# thundermaus.net
KiCad netlist of a schematic drawn in EAGLE
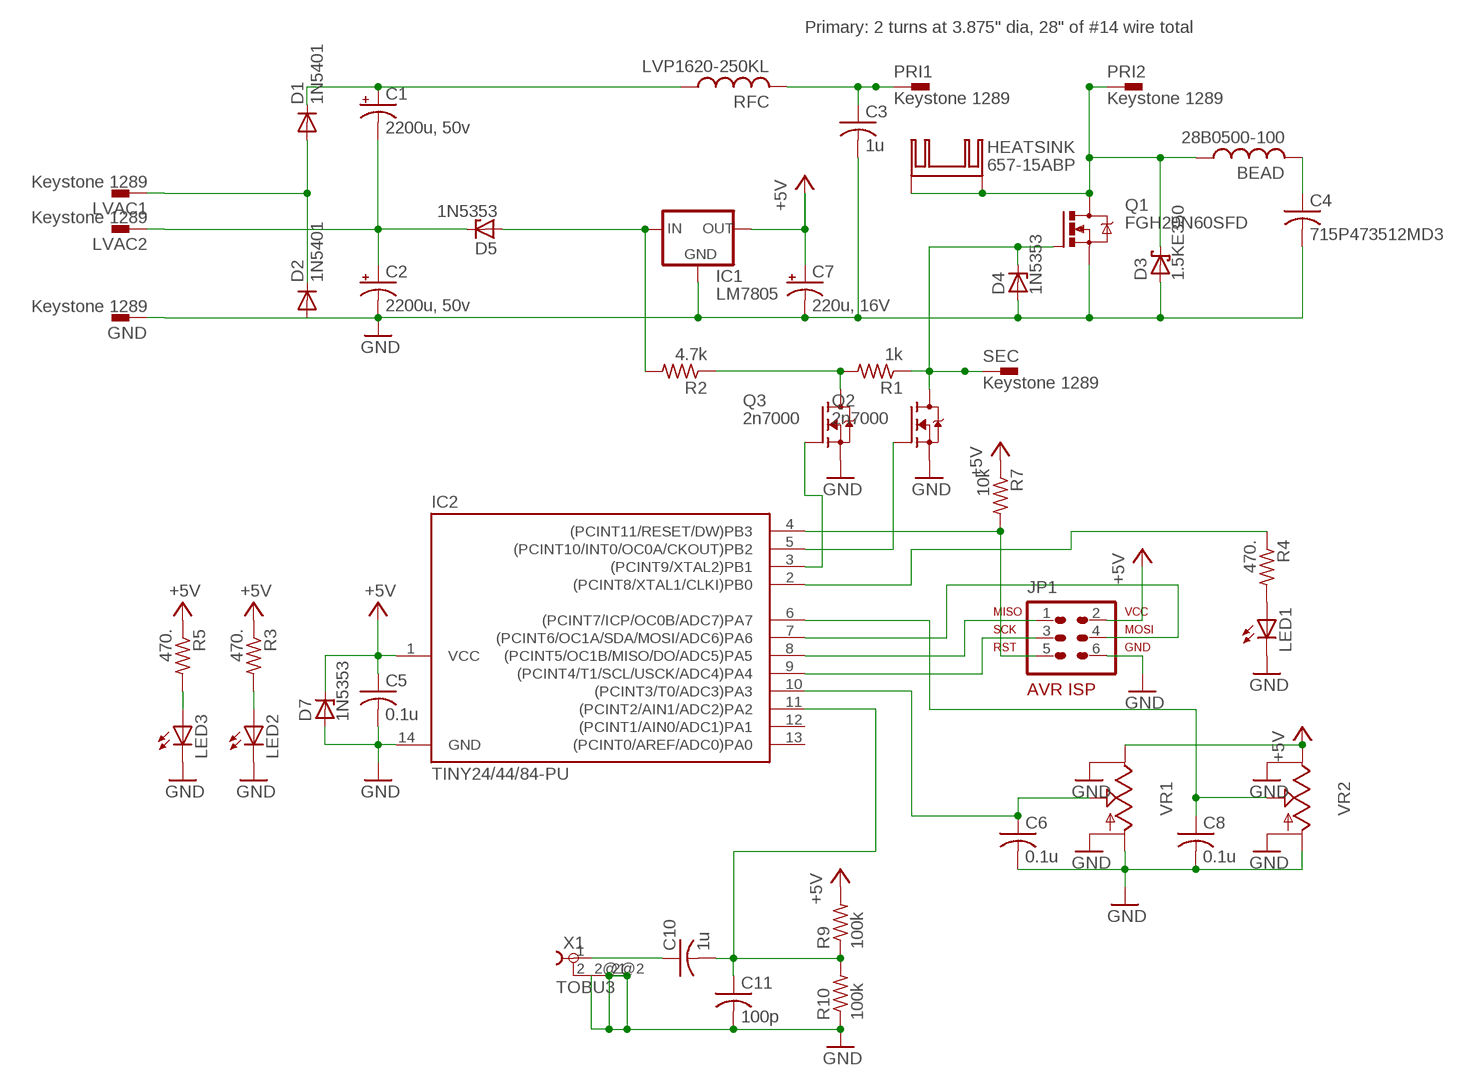
[diagram p0: schematic, sheet 1]

(export (version "E")
  (design (tool "Eeschema 10.0.6"))
  (components
    (comp (ref "BEAD")
      (value "28B0500-100")
      (footprint "eagle-import:0207_10")
      (libsource (lib "eagle-import") (part "L-US0207/10"))
    )
    (comp (ref "C1")
      (value "2200u, 50v")
      (footprint "eagle-import:E7,5-16")
      (libsource (lib "eagle-import") (part "CPOL-USE7.5-16"))
    )
    (comp (ref "C2")
      (value "2200u, 50v")
      (footprint "eagle-import:E7,5-16")
      (libsource (lib "eagle-import") (part "CPOL-USE7.5-16"))
    )
    (comp (ref "C3")
      (value "1u")
      (footprint "eagle-import:C225-062X268")
      (libsource (lib "eagle-import") (part "C-US225-062X268"))
    )
    (comp (ref "C4")
      (value "715P473512MD3")
      (footprint "eagle-import:C325-182X374")
      (libsource (lib "eagle-import") (part "C-US325-182X374"))
    )
    (comp (ref "C5")
      (value "0.1u")
      (footprint "eagle-import:C025-025X050")
      (libsource (lib "eagle-import") (part "C-US025-025X050"))
    )
    (comp (ref "C6")
      (value "0.1u")
      (footprint "eagle-import:C025-025X050")
      (libsource (lib "eagle-import") (part "C-US025-025X050"))
    )
    (comp (ref "C7")
      (value "220u, 16V")
      (footprint "eagle-import:E2,5-7")
      (libsource (lib "eagle-import") (part "CPOL-USE2.5-7"))
    )
    (comp (ref "C8")
      (value "0.1u")
      (footprint "eagle-import:C025-025X050")
      (libsource (lib "eagle-import") (part "C-US025-025X050"))
    )
    (comp (ref "C10")
      (value "1u")
      (footprint "eagle-import:C025-025X050")
      (libsource (lib "eagle-import") (part "C-US025-025X050"))
    )
    (comp (ref "C11")
      (value "100p")
      (footprint "eagle-import:C025-025X050")
      (libsource (lib "eagle-import") (part "C-US025-025X050"))
    )
    (comp (ref "D1")
      (value "1N5401")
      (footprint "eagle-import:DO201-15")
      (libsource (lib "eagle-import") (part "1N5400"))
    )
    (comp (ref "D2")
      (value "1N5401")
      (footprint "eagle-import:DO201-15")
      (libsource (lib "eagle-import") (part "1N5400"))
    )
    (comp (ref "D3")
      (value "1.5KE350")
      (footprint "eagle-import:DO201T15")
      (libsource (lib "eagle-import") (part "15KEXXD"))
    )
    (comp (ref "D4")
      (value "1N5353")
      (footprint "eagle-import:C1702-15")
      (libsource (lib "eagle-import") (part "1N5333"))
    )
    (comp (ref "D5")
      (value "1N5353")
      (footprint "eagle-import:C1702-15")
      (libsource (lib "eagle-import") (part "1N5333"))
    )
    (comp (ref "D7")
      (value "1N5353")
      (footprint "eagle-import:C1702-15")
      (libsource (lib "eagle-import") (part "1N5333"))
    )
    (comp (ref "GND")
      (value "Keystone 1289")
      (footprint "eagle-import:F061.060")
      (libsource (lib "eagle-import") (part "PIN2F061.060"))
    )
    (comp (ref "HEATSINK")
      (value "657-15ABP")
      (footprint "eagle-import:SK129")
      (libsource (lib "eagle-import") (part "SK129-PAD"))
    )
    (comp (ref "IC1")
      (value "LM7805")
      (footprint "eagle-import:78XXS")
      (libsource (lib "eagle-import") (part "78XXS"))
    )
    (comp (ref "IC2")
      (value "TINY24/44/84-PU")
      (footprint "eagle-import:DIL14")
      (libsource (lib "eagle-import") (part "TINY24/44/84-PU"))
    )
    (comp (ref "JP1")
      (value "AVR-ISP-6VERT")
      (footprint "eagle-import:AVR-ISP-6")
      (libsource (lib "eagle-import") (part "AVR-ISP-6VERT"))
    )
    (comp (ref "LED1")
      (value "LED5MM")
      (footprint "eagle-import:LED5MM")
      (libsource (lib "eagle-import") (part "LED5MM"))
    )
    (comp (ref "LED2")
      (value "LED5MM")
      (footprint "eagle-import:LED5MM")
      (libsource (lib "eagle-import") (part "LED5MM"))
    )
    (comp (ref "LED3")
      (value "LED5MM")
      (footprint "eagle-import:LED5MM")
      (libsource (lib "eagle-import") (part "LED5MM"))
    )
    (comp (ref "LVAC1")
      (value "Keystone 1289")
      (footprint "eagle-import:F061.060")
      (libsource (lib "eagle-import") (part "PIN2F061.060"))
    )
    (comp (ref "LVAC2")
      (value "Keystone 1289")
      (footprint "eagle-import:F061.060")
      (libsource (lib "eagle-import") (part "PIN2F061.060"))
    )
    (comp (ref "PRI1")
      (value "Keystone 1289")
      (footprint "eagle-import:F061.060")
      (libsource (lib "eagle-import") (part "PIN2F061.060"))
    )
    (comp (ref "PRI2")
      (value "Keystone 1289")
      (footprint "eagle-import:F061.060")
      (libsource (lib "eagle-import") (part "PIN2F061.060"))
    )
    (comp (ref "Q1")
      (value "FGH20N60SFD")
      (footprint "eagle-import:TO247BV")
      (libsource (lib "eagle-import") (part "IRFPC40"))
    )
    (comp (ref "Q2")
      (value "2n7000")
      (footprint "eagle-import:TO237-SW")
      (libsource (lib "eagle-import") (part "2N7000"))
    )
    (comp (ref "Q3")
      (value "2n7000")
      (footprint "eagle-import:TO237-SW")
      (libsource (lib "eagle-import") (part "2N7000"))
    )
    (comp (ref "R1")
      (value "1k")
      (footprint "eagle-import:0207_10")
      (libsource (lib "eagle-import") (part "R-US_0207/10"))
    )
    (comp (ref "R2")
      (value "4.7k")
      (footprint "eagle-import:0207_10")
      (libsource (lib "eagle-import") (part "R-US_0207/10"))
    )
    (comp (ref "R3")
      (value "470.")
      (footprint "eagle-import:0207_10")
      (libsource (lib "eagle-import") (part "R-US_0207/10"))
    )
    (comp (ref "R4")
      (value "470.")
      (footprint "eagle-import:0207_10")
      (libsource (lib "eagle-import") (part "R-US_0207/10"))
    )
    (comp (ref "R5")
      (value "470.")
      (footprint "eagle-import:0207_10")
      (libsource (lib "eagle-import") (part "R-US_0207/10"))
    )
    (comp (ref "R7")
      (value "10k")
      (footprint "eagle-import:0207_10")
      (libsource (lib "eagle-import") (part "R-US_0207/10"))
    )
    (comp (ref "R9")
      (value "100k")
      (footprint "eagle-import:0207_10")
      (libsource (lib "eagle-import") (part "R-US_0207/10"))
    )
    (comp (ref "R10")
      (value "100k")
      (footprint "eagle-import:0207_10")
      (libsource (lib "eagle-import") (part "R-US_0207/10"))
    )
    (comp (ref "RFC")
      (value "LVP1620-250KL")
      (footprint "eagle-import:TJ4-U1")
      (libsource (lib "eagle-import") (part "L-USTJ4-U1"))
    )
    (comp (ref "SEC")
      (value "Keystone 1289")
      (footprint "eagle-import:F061.060")
      (libsource (lib "eagle-import") (part "PIN2F061.060"))
    )
    (comp (ref "VR1")
      (value "PTV09")
      (footprint "eagle-import:PTV09")
      (libsource (lib "eagle-import") (part "PTV09"))
    )
    (comp (ref "VR2")
      (value "PTV09")
      (footprint "eagle-import:PTV09")
      (libsource (lib "eagle-import") (part "PTV09"))
    )
    (comp (ref "X1")
      (value "TOBU3")
      (footprint "eagle-import:TOBU3")
      (libsource (lib "eagle-import") (part "TOBU3"))
    )
  )
  (nets
    (net (code "1") (name "+5V") (class "Default")
      (node (ref "C5") (pin "1") (pinfunction "1_1") (pintype "passive"))
      (node (ref "C7") (pin "+") (pinfunction "+_+") (pintype "passive"))
      (node (ref "D7") (pin "C") (pinfunction "C_C") (pintype "passive"))
      (node (ref "IC1") (pin "OUT") (pinfunction "OUT_OUT") (pintype "passive"))
      (node (ref "IC2") (pin "1") (pinfunction "VCC_1") (pintype "power_in"))
      (node (ref "JP1") (pin "2") (pinfunction "2_2") (pintype "passive"))
      (node (ref "R3") (pin "1") (pinfunction "1_1") (pintype "passive"))
      (node (ref "R5") (pin "1") (pinfunction "1_1") (pintype "passive"))
      (node (ref "R7") (pin "1") (pinfunction "1_1") (pintype "passive"))
      (node (ref "R9") (pin "2") (pinfunction "2_2") (pintype "passive"))
      (node (ref "VR1") (pin "P1") (pinfunction "E_P1") (pintype "passive"))
      (node (ref "VR2") (pin "P1") (pinfunction "E_P1") (pintype "passive"))
    )
    (net (code "2") (name "GND") (class "Default")
      (node (ref "C11") (pin "2") (pinfunction "2_2") (pintype "passive"))
      (node (ref "C2") (pin "-") (pinfunction "-_-") (pintype "passive"))
      (node (ref "C3") (pin "2") (pinfunction "2_2") (pintype "passive"))
      (node (ref "C4") (pin "2") (pinfunction "2_2") (pintype "passive"))
      (node (ref "C5") (pin "2") (pinfunction "2_2") (pintype "passive"))
      (node (ref "C6") (pin "2") (pinfunction "2_2") (pintype "passive"))
      (node (ref "C7") (pin "-") (pinfunction "-_-") (pintype "passive"))
      (node (ref "C8") (pin "2") (pinfunction "2_2") (pintype "passive"))
      (node (ref "D2") (pin "A") (pinfunction "A_A") (pintype "passive"))
      (node (ref "D3") (pin "A") (pinfunction "A_A") (pintype "passive"))
      (node (ref "D4") (pin "A") (pinfunction "A_A") (pintype "passive"))
      (node (ref "D7") (pin "A") (pinfunction "A_A") (pintype "passive"))
      (node (ref "GND") (pin "A1") (pinfunction "1_A1") (pintype "passive"))
      (node (ref "GND") (pin "A2") (pinfunction "1.1_A2") (pintype "passive"))
      (node (ref "IC1") (pin "GND") (pinfunction "GND_GND") (pintype "input"))
      (node (ref "IC2") (pin "14") (pinfunction "GND_14") (pintype "power_in"))
      (node (ref "JP1") (pin "6") (pinfunction "6_6") (pintype "passive"))
      (node (ref "LED1") (pin "K") (pinfunction "C_K") (pintype "passive"))
      (node (ref "LED2") (pin "K") (pinfunction "C_K") (pintype "passive"))
      (node (ref "LED3") (pin "K") (pinfunction "C_K") (pintype "passive"))
      (node (ref "Q1") (pin "S") (pinfunction "S_S") (pintype "passive"))
      (node (ref "Q2") (pin "3") (pinfunction "S_3") (pintype "passive"))
      (node (ref "Q3") (pin "3") (pinfunction "S_3") (pintype "passive"))
      (node (ref "R10") (pin "1") (pinfunction "1_1") (pintype "passive"))
      (node (ref "VR1") (pin "P$4") (pinfunction "P$2_P$4") (pintype "passive"))
      (node (ref "VR1") (pin "P$5") (pinfunction "P$1_P$5") (pintype "passive"))
      (node (ref "VR1") (pin "P3") (pinfunction "A_P3") (pintype "passive"))
      (node (ref "VR2") (pin "P$4") (pinfunction "P$2_P$4") (pintype "passive"))
      (node (ref "VR2") (pin "P$5") (pinfunction "P$1_P$5") (pintype "passive"))
      (node (ref "VR2") (pin "P3") (pinfunction "A_P3") (pintype "passive"))
      (node (ref "X1") (pin "2") (pinfunction "2_2") (pintype "passive"))
      (node (ref "X1") (pin "2@1") (pinfunction "3_2@1") (pintype "passive"))
      (node (ref "X1") (pin "2@2") (pinfunction "4_2@2") (pintype "passive"))
    )
    (net (code "3") (name "Net-(BEAD-Pad2)") (class "Default")
      (node (ref "BEAD") (pin "2") (pinfunction "2_2") (pintype "passive"))
      (node (ref "C4") (pin "1") (pinfunction "1_1") (pintype "passive"))
    )
    (net (code "4") (name "Net-(C1-Pad+)") (class "Default")
      (node (ref "C1") (pin "+") (pinfunction "+_+") (pintype "passive"))
      (node (ref "D1") (pin "C") (pinfunction "C_C") (pintype "passive"))
      (node (ref "RFC") (pin "1") (pinfunction "1_1") (pintype "passive"))
    )
    (net (code "5") (name "Net-(C10-Pad1)") (class "Default")
      (node (ref "C10") (pin "1") (pinfunction "1_1") (pintype "passive"))
      (node (ref "X1") (pin "1") (pinfunction "1_1") (pintype "passive"))
    )
    (net (code "6") (name "Net-(D5-PadA)") (class "Default")
      (node (ref "D5") (pin "A") (pinfunction "A_A") (pintype "passive"))
      (node (ref "IC1") (pin "IN") (pinfunction "IN_IN") (pintype "input"))
      (node (ref "R2") (pin "2") (pinfunction "2_2") (pintype "passive"))
    )
    (net (code "7") (name "Net-(IC2-(PCINT2{slash}AIN1{slash}ADC2)PA2)") (class "Default")
      (node (ref "C10") (pin "2") (pinfunction "2_2") (pintype "passive"))
      (node (ref "C11") (pin "1") (pinfunction "1_1") (pintype "passive"))
      (node (ref "IC2") (pin "11") (pinfunction "(PCINT2/AIN1/ADC2)PA2_11") (pintype "bidirectional"))
      (node (ref "R10") (pin "2") (pinfunction "2_2") (pintype "passive"))
      (node (ref "R9") (pin "1") (pinfunction "1_1") (pintype "passive"))
    )
    (net (code "8") (name "Net-(IC2-(PCINT3{slash}T0{slash}ADC3)PA3)") (class "Default")
      (node (ref "C6") (pin "1") (pinfunction "1_1") (pintype "passive"))
      (node (ref "IC2") (pin "10") (pinfunction "(PCINT3/T0/ADC3)PA3_10") (pintype "bidirectional"))
      (node (ref "VR1") (pin "P2") (pinfunction "S_P2") (pintype "passive"))
    )
    (net (code "9") (name "Net-(IC2-(PCINT4{slash}T1{slash}SCL{slash}USCK{slash}ADC4)PA4)") (class "Default")
      (node (ref "IC2") (pin "9") (pinfunction "(PCINT4/T1/SCL/USCK/ADC4)PA4_9") (pintype "bidirectional"))
      (node (ref "JP1") (pin "3") (pinfunction "3_3") (pintype "passive"))
    )
    (net (code "10") (name "Net-(IC2-(PCINT5{slash}OC1B{slash}MISO{slash}DO{slash}ADC5)PA5)") (class "Default")
      (node (ref "IC2") (pin "8") (pinfunction "(PCINT5/OC1B/MISO/DO/ADC5)PA5_8") (pintype "bidirectional"))
      (node (ref "JP1") (pin "1") (pinfunction "1_1") (pintype "passive"))
    )
    (net (code "11") (name "Net-(IC2-(PCINT6{slash}OC1A{slash}SDA{slash}MOSI{slash}ADC6)PA6)") (class "Default")
      (node (ref "IC2") (pin "7") (pinfunction "(PCINT6/OC1A/SDA/MOSI/ADC6)PA6_7") (pintype "bidirectional"))
      (node (ref "JP1") (pin "4") (pinfunction "4_4") (pintype "passive"))
    )
    (net (code "12") (name "Net-(IC2-(PCINT7{slash}ICP{slash}OC0B{slash}ADC7)PA7)") (class "Default")
      (node (ref "C8") (pin "1") (pinfunction "1_1") (pintype "passive"))
      (node (ref "IC2") (pin "6") (pinfunction "(PCINT7/ICP/OC0B/ADC7)PA7_6") (pintype "bidirectional"))
      (node (ref "VR2") (pin "P2") (pinfunction "S_P2") (pintype "passive"))
    )
    (net (code "13") (name "Net-(IC2-(PCINT8{slash}XTAL1{slash}CLKI)PB0)") (class "Default")
      (node (ref "IC2") (pin "2") (pinfunction "(PCINT8/XTAL1/CLKI)PB0_2") (pintype "bidirectional"))
      (node (ref "R4") (pin "1") (pinfunction "1_1") (pintype "passive"))
    )
    (net (code "14") (name "Net-(IC2-(PCINT9{slash}XTAL2)PB1)") (class "Default")
      (node (ref "IC2") (pin "3") (pinfunction "(PCINT9/XTAL2)PB1_3") (pintype "bidirectional"))
      (node (ref "Q3") (pin "2") (pinfunction "G_2") (pintype "passive"))
    )
    (net (code "15") (name "Net-(IC2-(PCINT10{slash}INT0{slash}OC0A{slash}CKOUT)PB2)") (class "Default")
      (node (ref "IC2") (pin "5") (pinfunction "(PCINT10/INT0/OC0A/CKOUT)PB2_5") (pintype "bidirectional"))
      (node (ref "Q2") (pin "2") (pinfunction "G_2") (pintype "passive"))
    )
    (net (code "16") (name "Net-(IC2-(PCINT11{slash}RESET{slash}DW)PB3)") (class "Default")
      (node (ref "IC2") (pin "4") (pinfunction "(PCINT11/RESET/DW)PB3_4") (pintype "bidirectional"))
      (node (ref "JP1") (pin "5") (pinfunction "5_5") (pintype "passive"))
      (node (ref "R7") (pin "2") (pinfunction "2_2") (pintype "passive"))
    )
    (net (code "17") (name "Net-(LED1-PadA)") (class "Default")
      (node (ref "LED1") (pin "A") (pinfunction "A_A") (pintype "passive"))
      (node (ref "R4") (pin "2") (pinfunction "2_2") (pintype "passive"))
    )
    (net (code "18") (name "Net-(LED2-PadA)") (class "Default")
      (node (ref "LED2") (pin "A") (pinfunction "A_A") (pintype "passive"))
      (node (ref "R3") (pin "2") (pinfunction "2_2") (pintype "passive"))
    )
    (net (code "19") (name "Net-(LED3-PadA)") (class "Default")
      (node (ref "LED3") (pin "A") (pinfunction "A_A") (pintype "passive"))
      (node (ref "R5") (pin "2") (pinfunction "2_2") (pintype "passive"))
    )
    (net (code "20") (name "Net-(LVAC1-1)") (class "Default")
      (node (ref "D1") (pin "A") (pinfunction "A_A") (pintype "passive"))
      (node (ref "D2") (pin "C") (pinfunction "C_C") (pintype "passive"))
      (node (ref "LVAC1") (pin "A1") (pinfunction "1_A1") (pintype "passive"))
      (node (ref "LVAC1") (pin "A2") (pinfunction "1.1_A2") (pintype "passive"))
    )
    (net (code "21") (name "Net-(LVAC2-1)") (class "Default")
      (node (ref "C1") (pin "-") (pinfunction "-_-") (pintype "passive"))
      (node (ref "C2") (pin "+") (pinfunction "+_+") (pintype "passive"))
      (node (ref "D5") (pin "C") (pinfunction "C_C") (pintype "passive"))
      (node (ref "LVAC2") (pin "A1") (pinfunction "1_A1") (pintype "passive"))
      (node (ref "LVAC2") (pin "A2") (pinfunction "1.1_A2") (pintype "passive"))
    )
    (net (code "22") (name "Net-(PRI1-1)") (class "Default")
      (node (ref "C3") (pin "1") (pinfunction "1_1") (pintype "passive"))
      (node (ref "PRI1") (pin "A1") (pinfunction "1_A1") (pintype "passive"))
      (node (ref "PRI1") (pin "A2") (pinfunction "1.1_A2") (pintype "passive"))
      (node (ref "RFC") (pin "2") (pinfunction "2_2") (pintype "passive"))
    )
    (net (code "23") (name "Net-(PRI2-1)") (class "Default")
      (node (ref "BEAD") (pin "1") (pinfunction "1_1") (pintype "passive"))
      (node (ref "D3") (pin "C") (pinfunction "C_C") (pintype "passive"))
      (node (ref "HEATSINK") (pin "A2,5") (pinfunction "K_A2,5") (pintype "passive"))
      (node (ref "HEATSINK") (pin "B2,5") (pinfunction "K_B2,5") (pintype "passive"))
      (node (ref "PRI2") (pin "A1") (pinfunction "1_A1") (pintype "passive"))
      (node (ref "PRI2") (pin "A2") (pinfunction "1.1_A2") (pintype "passive"))
      (node (ref "Q1") (pin "D") (pinfunction "D_D") (pintype "passive"))
    )
    (net (code "24") (name "Net-(Q2-D)") (class "Default")
      (node (ref "D4") (pin "C") (pinfunction "C_C") (pintype "passive"))
      (node (ref "Q1") (pin "G") (pinfunction "G_G") (pintype "passive"))
      (node (ref "Q2") (pin "1") (pinfunction "D_1") (pintype "passive"))
      (node (ref "R1") (pin "1") (pinfunction "1_1") (pintype "passive"))
      (node (ref "SEC") (pin "A1") (pinfunction "1_A1") (pintype "passive"))
      (node (ref "SEC") (pin "A2") (pinfunction "1.1_A2") (pintype "passive"))
    )
    (net (code "25") (name "Net-(Q3-D)") (class "Default")
      (node (ref "Q3") (pin "1") (pinfunction "D_1") (pintype "passive"))
      (node (ref "R1") (pin "2") (pinfunction "2_2") (pintype "passive"))
      (node (ref "R2") (pin "1") (pinfunction "1_1") (pintype "passive"))
    )
    (net (code "26") (name "unconnected-(IC2-(PCINT0{slash}AREF{slash}ADC0)PA0-Pad13)") (class "Default")
      (node (ref "IC2") (pin "13") (pinfunction "(PCINT0/AREF/ADC0)PA0_13") (pintype "bidirectional"))
    )
    (net (code "27") (name "unconnected-(IC2-(PCINT1{slash}AIN0{slash}ADC1)PA1-Pad12)") (class "Default")
      (node (ref "IC2") (pin "12") (pinfunction "(PCINT1/AIN0/ADC1)PA1_12") (pintype "bidirectional"))
    )
  )
)
